# RF_Splitter.net
KiCad netlist of a schematic drawn in EAGLE
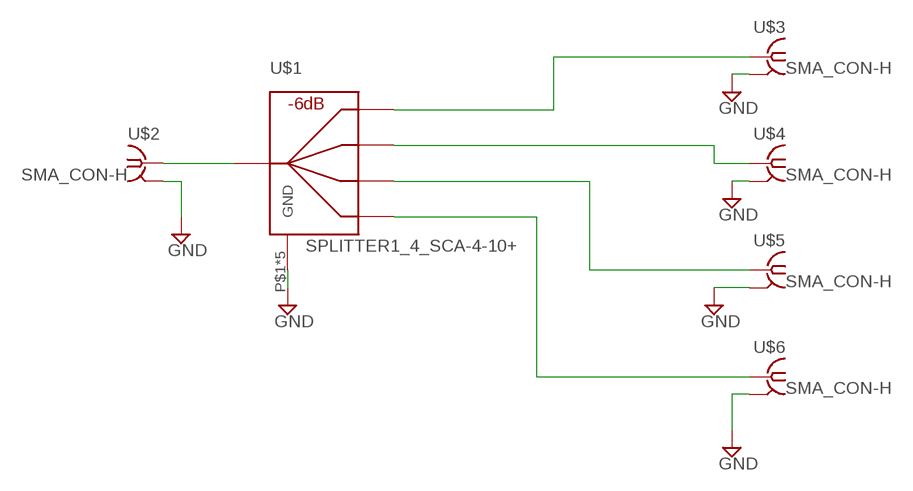
[diagram p0: schematic, sheet 1]

(export (version "E")
  (design (tool "Eeschema 10.0.6"))
  (components
    (comp (ref "U$1")
      (value "SPLITTER1_4_SCA-4-10+")
      (footprint "eagle-import:SCA-4-10+")
      (libsource (lib "eagle-import") (part "SPLITTER1_4_SCA-4-10+"))
    )
    (comp (ref "U$2")
      (value "SMA_CON-H")
      (footprint "eagle-import:BU-SMA-H")
      (libsource (lib "eagle-import") (part "SMA_CON-H"))
    )
    (comp (ref "U$3")
      (value "SMA_CON-H")
      (footprint "eagle-import:BU-SMA-H")
      (libsource (lib "eagle-import") (part "SMA_CON-H"))
    )
    (comp (ref "U$4")
      (value "SMA_CON-H")
      (footprint "eagle-import:BU-SMA-H")
      (libsource (lib "eagle-import") (part "SMA_CON-H"))
    )
    (comp (ref "U$5")
      (value "SMA_CON-H")
      (footprint "eagle-import:BU-SMA-H")
      (libsource (lib "eagle-import") (part "SMA_CON-H"))
    )
    (comp (ref "U$6")
      (value "SMA_CON-H")
      (footprint "eagle-import:BU-SMA-H")
      (libsource (lib "eagle-import") (part "SMA_CON-H"))
    )
  )
  (nets
    (net (code "1") (name "GND") (class "Default")
      (node (ref "U$1") (pin "P$1") (pinfunction "GND_P$1") (pintype "bidirectional"))
      (node (ref "U$1") (pin "P$2") (pinfunction "GND_P$2") (pintype "bidirectional"))
      (node (ref "U$1") (pin "P$4") (pinfunction "GND_P$4") (pintype "bidirectional"))
      (node (ref "U$1") (pin "P$5") (pinfunction "GND_P$5") (pintype "bidirectional"))
      (node (ref "U$1") (pin "P$8") (pinfunction "GND_P$8") (pintype "bidirectional"))
      (node (ref "U$2") (pin "2") (pinfunction "GND_2") (pintype "passive"))
      (node (ref "U$2") (pin "3") (pinfunction "GND_3") (pintype "passive"))
      (node (ref "U$2") (pin "4") (pinfunction "GND_4") (pintype "passive"))
      (node (ref "U$2") (pin "5") (pinfunction "GND_5") (pintype "passive"))
      (node (ref "U$3") (pin "2") (pinfunction "GND_2") (pintype "passive"))
      (node (ref "U$3") (pin "3") (pinfunction "GND_3") (pintype "passive"))
      (node (ref "U$3") (pin "4") (pinfunction "GND_4") (pintype "passive"))
      (node (ref "U$3") (pin "5") (pinfunction "GND_5") (pintype "passive"))
      (node (ref "U$4") (pin "2") (pinfunction "GND_2") (pintype "passive"))
      (node (ref "U$4") (pin "3") (pinfunction "GND_3") (pintype "passive"))
      (node (ref "U$4") (pin "4") (pinfunction "GND_4") (pintype "passive"))
      (node (ref "U$4") (pin "5") (pinfunction "GND_5") (pintype "passive"))
      (node (ref "U$5") (pin "2") (pinfunction "GND_2") (pintype "passive"))
      (node (ref "U$5") (pin "3") (pinfunction "GND_3") (pintype "passive"))
      (node (ref "U$5") (pin "4") (pinfunction "GND_4") (pintype "passive"))
      (node (ref "U$5") (pin "5") (pinfunction "GND_5") (pintype "passive"))
      (node (ref "U$6") (pin "2") (pinfunction "GND_2") (pintype "passive"))
      (node (ref "U$6") (pin "3") (pinfunction "GND_3") (pintype "passive"))
      (node (ref "U$6") (pin "4") (pinfunction "GND_4") (pintype "passive"))
      (node (ref "U$6") (pin "5") (pinfunction "GND_5") (pintype "passive"))
    )
    (net (code "2") (name "Net-(U$1-P$1)") (class "Default")
      (node (ref "U$1") (pin "P$3") (pinfunction "P$1_P$3") (pintype "bidirectional"))
      (node (ref "U$2") (pin "1") (pinfunction "1_1") (pintype "passive"))
    )
    (net (code "3") (name "Net-(U$1-P$2)") (class "Default")
      (node (ref "U$1") (pin "P$6") (pinfunction "P$2_P$6") (pintype "bidirectional"))
      (node (ref "U$3") (pin "1") (pinfunction "1_1") (pintype "passive"))
    )
    (net (code "4") (name "Net-(U$1-P$3)") (class "Default")
      (node (ref "U$1") (pin "P$7") (pinfunction "P$3_P$7") (pintype "bidirectional"))
      (node (ref "U$4") (pin "1") (pinfunction "1_1") (pintype "passive"))
    )
    (net (code "5") (name "Net-(U$1-P$4)") (class "Default")
      (node (ref "U$1") (pin "P$9") (pinfunction "P$4_P$9") (pintype "bidirectional"))
      (node (ref "U$5") (pin "1") (pinfunction "1_1") (pintype "passive"))
    )
    (net (code "6") (name "Net-(U$1-P$5)") (class "Default")
      (node (ref "U$1") (pin "P$10") (pinfunction "P$5_P$10") (pintype "bidirectional"))
      (node (ref "U$6") (pin "1") (pinfunction "1_1") (pintype "passive"))
    )
  )
)
